# 10_LMS3_RF.net
KiCad netlist of a schematic drawn in Altium Designer
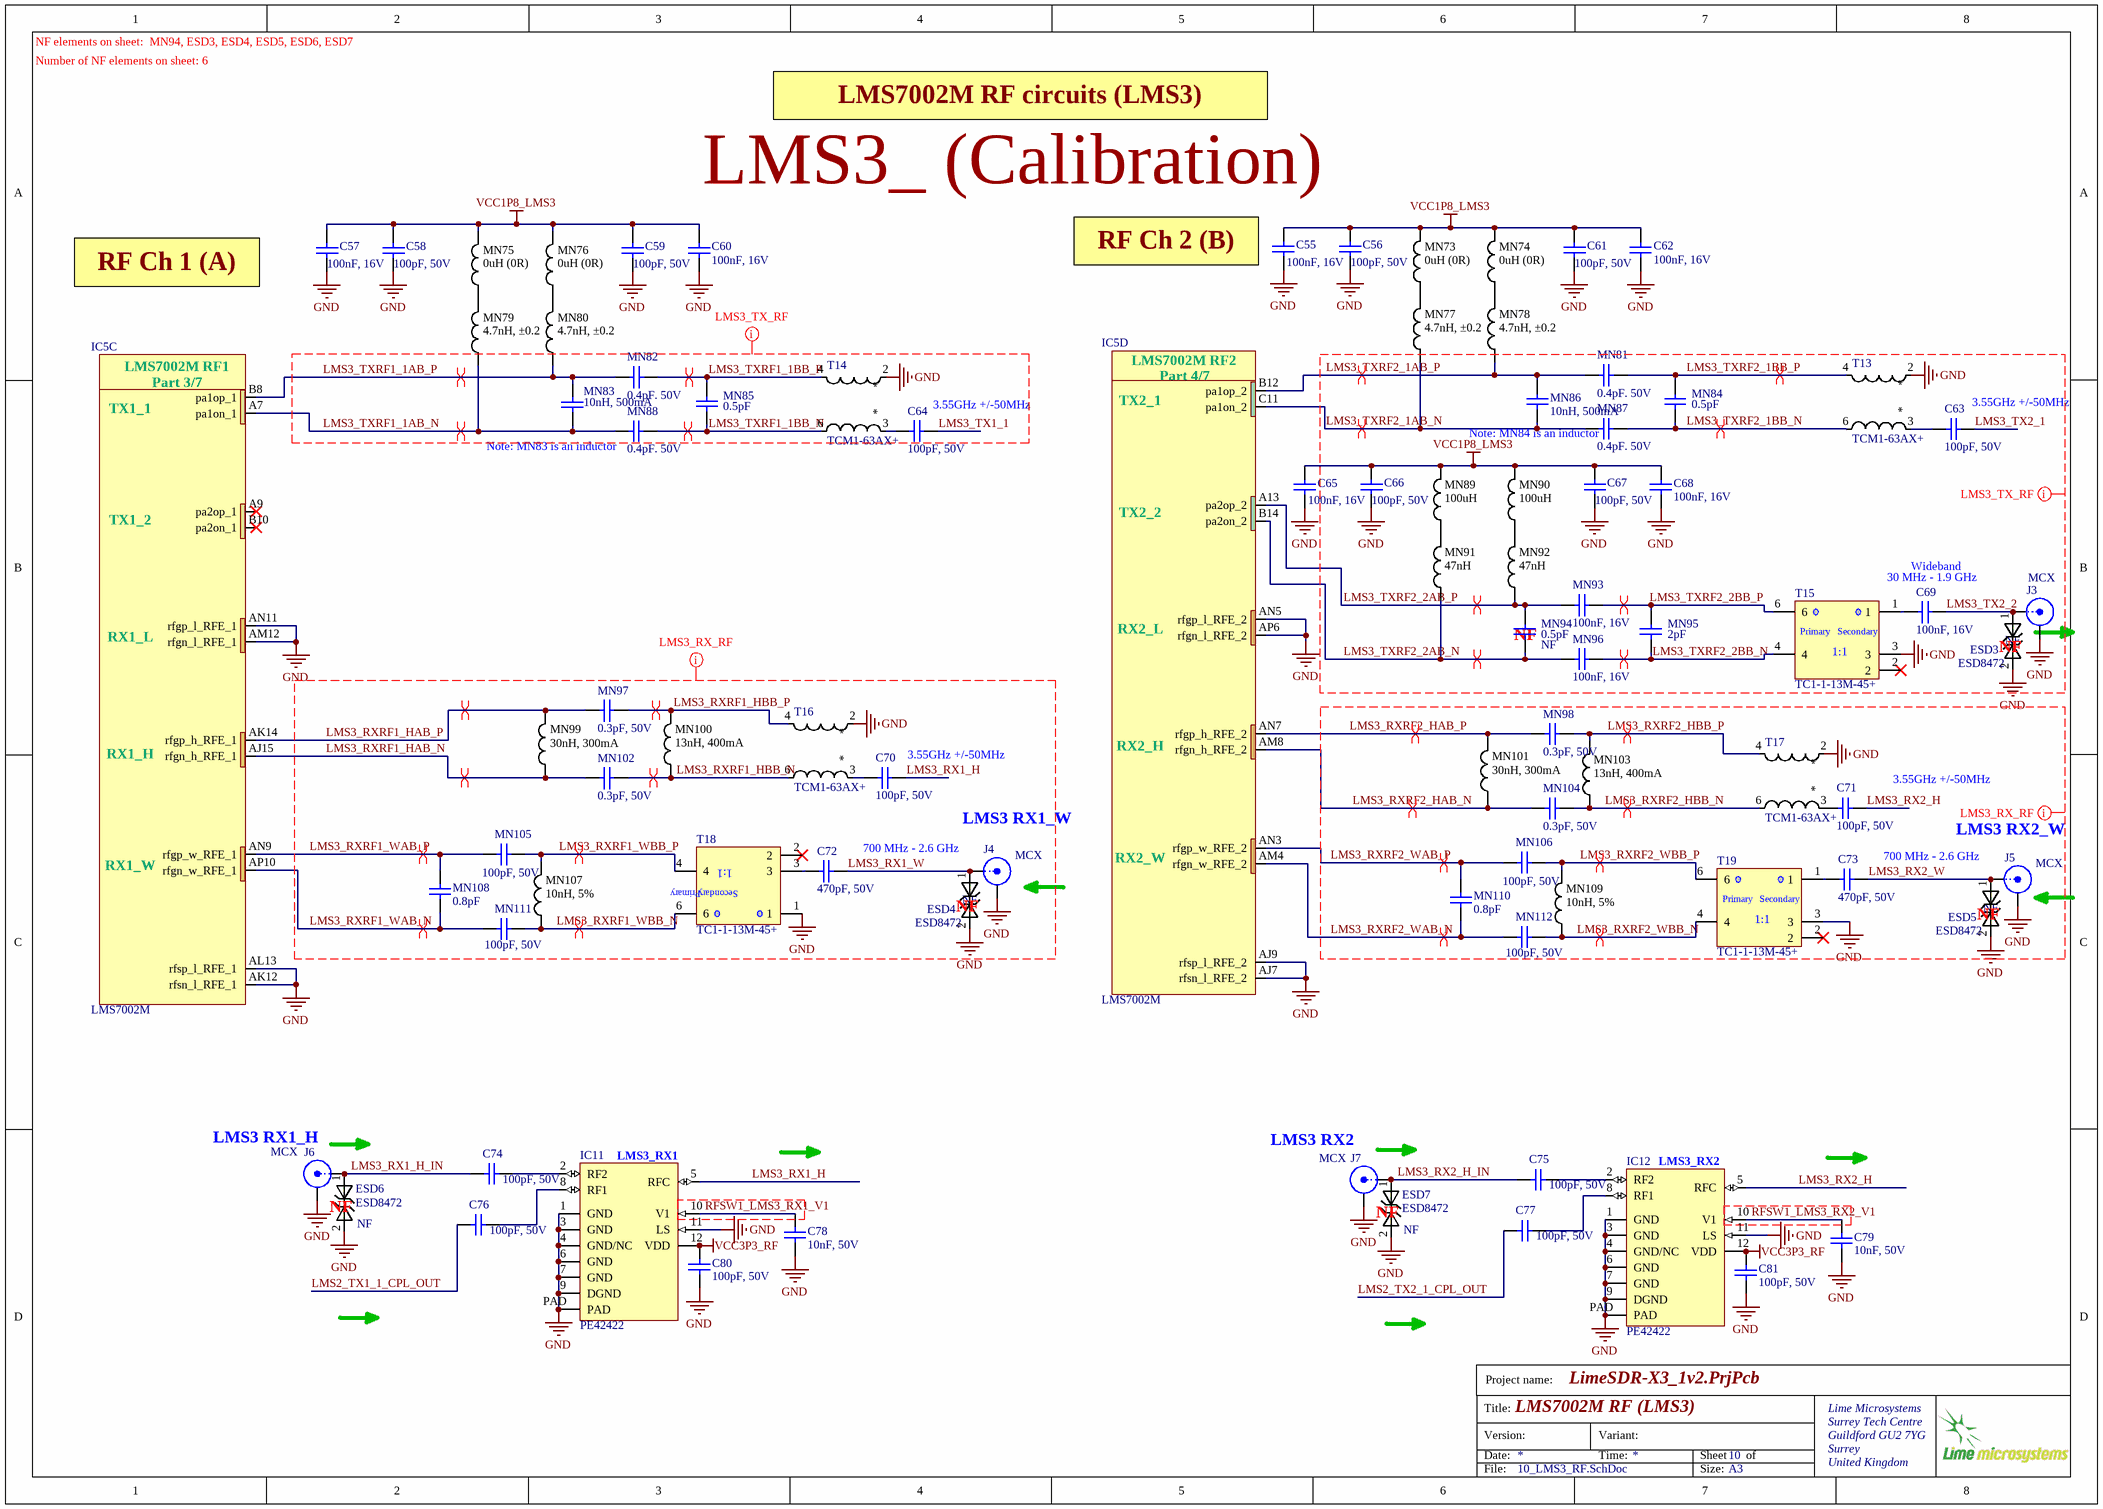
[diagram p0: 10_LMS3_RF.SchDoc]

(export (version "E")
  (design (tool "Eeschema 10.0.6"))
  (components
    (comp (ref "C55")
      (value "100nF, 16V")
      (footprint "CAP0402")
      (fields (field (name "MANUFACTURER") "Murata Electronics") (field (name "TOLERANCE") "10 %"))
      (libsource (lib "") (part "Cap_0402_9"))
    )
    (comp (ref "C56")
      (value "100pF, 50V")
      (footprint "CAP0402")
      (fields (field (name "MANUFACTURER") "Yageo") (field (name "TOLERANCE") "±5%"))
      (libsource (lib "") (part "Cap_0402_5"))
    )
    (comp (ref "C57")
      (value "100nF, 16V")
      (footprint "CAP0402")
      (fields (field (name "MANUFACTURER") "Murata Electronics") (field (name "TOLERANCE") "10 %"))
      (libsource (lib "") (part "Cap_0402_1"))
    )
    (comp (ref "C58")
      (value "100pF, 50V")
      (footprint "CAP0402")
      (fields (field (name "MANUFACTURER") "Yageo") (field (name "TOLERANCE") "±5%"))
      (libsource (lib "") (part "Cap_0402_5"))
    )
    (comp (ref "C59")
      (value "100pF, 50V")
      (footprint "CAP0402")
      (fields (field (name "MANUFACTURER") "Yageo") (field (name "TOLERANCE") "±5%"))
      (libsource (lib "") (part "Cap_0402_5"))
    )
    (comp (ref "C60")
      (value "100nF, 16V")
      (footprint "CAP0402")
      (fields (field (name "MANUFACTURER") "Murata Electronics") (field (name "TOLERANCE") "10 %"))
      (libsource (lib "") (part "Cap_0402_1"))
    )
    (comp (ref "C61")
      (value "100pF, 50V")
      (footprint "CAP0402")
      (fields (field (name "MANUFACTURER") "Yageo") (field (name "TOLERANCE") "±5%"))
      (libsource (lib "") (part "Cap_0402_5"))
    )
    (comp (ref "C62")
      (value "100nF, 16V")
      (footprint "CAP0402")
      (fields (field (name "MANUFACTURER") "Murata Electronics") (field (name "TOLERANCE") "10 %"))
      (libsource (lib "") (part "Cap_0402_9"))
    )
    (comp (ref "C63")
      (value "100pF, 50V")
      (footprint "CAP0402")
      (fields (field (name "TOLERANCE") "±5%") (field (name "MANUFACTURER") "Yageo"))
      (libsource (lib "") (part "Cap_0402_5"))
    )
    (comp (ref "C64")
      (value "100pF, 50V")
      (footprint "CAP0402")
      (fields (field (name "TOLERANCE") "±5%") (field (name "MANUFACTURER") "Yageo"))
      (libsource (lib "") (part "Cap_0402_5"))
    )
    (comp (ref "C65")
      (value "100nF, 16V")
      (footprint "CAP0402")
      (fields (field (name "MANUFACTURER") "Murata Electronics") (field (name "TOLERANCE") "10 %"))
      (libsource (lib "") (part "Cap_0402_6"))
    )
    (comp (ref "C66")
      (value "100pF, 50V")
      (footprint "CAP0402")
      (fields (field (name "MANUFACTURER") "Yageo") (field (name "TOLERANCE") "±5%"))
      (libsource (lib "") (part "Cap_0402_5"))
    )
    (comp (ref "C67")
      (value "100pF, 50V")
      (footprint "CAP0402")
      (fields (field (name "MANUFACTURER") "Yageo") (field (name "TOLERANCE") "±5%"))
      (libsource (lib "") (part "Cap_0402_5"))
    )
    (comp (ref "C68")
      (value "100nF, 16V")
      (footprint "CAP0402")
      (fields (field (name "MANUFACTURER") "Murata Electronics") (field (name "TOLERANCE") "10 %"))
      (libsource (lib "") (part "Cap_0402_6"))
    )
    (comp (ref "C69")
      (value "100nF, 16V")
      (footprint "CAP0402")
      (fields (field (name "MANUFACTURER") "Murata Electronics") (field (name "TOLERANCE") "10 %"))
      (libsource (lib "") (part "Cap_0402_12"))
    )
    (comp (ref "C70")
      (value "100pF, 50V")
      (footprint "CAP0402")
      (fields (field (name "TOLERANCE") "±5%") (field (name "MANUFACTURER") "Yageo"))
      (libsource (lib "LimeMicroAltiumLib_schLib") (part "Cap_0402"))
    )
    (comp (ref "C71")
      (value "100pF, 50V")
      (footprint "CAP0402")
      (fields (field (name "TOLERANCE") "±5%") (field (name "MANUFACTURER") "Yageo"))
      (libsource (lib "LimeMicroAltiumLib_schLib") (part "Cap_0402"))
    )
    (comp (ref "C72")
      (value "470pF, 50V")
      (footprint "CAP0402")
      (fields
        (field (name "MANUFACTURER PART NUMBER") "C1005C0G1H471J050BA")
        (field (name "TOLERANCE") "±5%")
        (field (name "MANUFACTURER") "TDK Corporation")
      )
      (libsource (lib "") (part "Cap_0402_4"))
    )
    (comp (ref "C73")
      (value "470pF, 50V")
      (footprint "CAP0402")
      (fields
        (field (name "MANUFACTURER PART NUMBER") "C1005C0G1H471J050BA")
        (field (name "TOLERANCE") "±5%")
        (field (name "MANUFACTURER") "TDK Corporation")
      )
      (libsource (lib "") (part "Cap_0402_4"))
    )
    (comp (ref "C74")
      (value "100pF, 50V")
      (footprint "CAP0402")
      (fields (field (name "TOLERANCE") "±5%") (field (name "MANUFACTURER") "Yageo"))
      (libsource (lib "") (part "Cap_0402_7"))
    )
    (comp (ref "C75")
      (value "100pF, 50V")
      (footprint "CAP0402")
      (fields (field (name "TOLERANCE") "±5%") (field (name "MANUFACTURER") "Yageo"))
      (libsource (lib "") (part "Cap_0402_7"))
    )
    (comp (ref "C76")
      (value "100pF, 50V")
      (footprint "CAP0402")
      (fields (field (name "TOLERANCE") "±5%") (field (name "MANUFACTURER") "Yageo"))
      (libsource (lib "") (part "Cap_0402_7"))
    )
    (comp (ref "C77")
      (value "100pF, 50V")
      (footprint "CAP0402")
      (fields (field (name "TOLERANCE") "±5%") (field (name "MANUFACTURER") "Yageo"))
      (libsource (lib "") (part "Cap_0402_7"))
    )
    (comp (ref "C78")
      (value "10nF, 50V")
      (footprint "CAP0402")
      (fields
        (field (name "MANUFACTURER") "Murata Electronics North America")
        (field (name "TOLERANCE") "±10%")
      )
      (libsource (lib "") (part "Cap_0402_1"))
    )
    (comp (ref "C79")
      (value "10nF, 50V")
      (footprint "CAP0402")
      (fields
        (field (name "MANUFACTURER") "Murata Electronics North America")
        (field (name "TOLERANCE") "±10%")
      )
      (libsource (lib "") (part "Cap_0402_1"))
    )
    (comp (ref "C80")
      (value "100pF, 50V")
      (footprint "CAP0402")
      (fields (field (name "TOLERANCE") "±5%") (field (name "MANUFACTURER") "Yageo"))
      (libsource (lib "") (part "Cap_0402_10"))
    )
    (comp (ref "C81")
      (value "100pF, 50V")
      (footprint "CAP0402")
      (fields (field (name "TOLERANCE") "±5%") (field (name "MANUFACTURER") "Yageo"))
      (libsource (lib "") (part "Cap_0402_10"))
    )
    (comp (ref "ESD3")
      (value "ESD8472")
      (footprint "ESD8472_X3DFN2")
      (fields (field (name "MANUFACTURER") "ON Semiconductor") (field (name "ASSEMBLY INFO") "NF"))
      (libsource (lib "LimeMicroAltiumLib_schLib") (part "ESD8472"))
    )
    (comp (ref "ESD4")
      (value "ESD8472")
      (footprint "ESD8472_X3DFN2")
      (fields (field (name "MANUFACTURER") "ON Semiconductor") (field (name "ASSEMBLY INFO") "NF"))
      (libsource (lib "LimeMicroAltiumLib_schLib") (part "ESD8472"))
    )
    (comp (ref "ESD5")
      (value "ESD8472")
      (footprint "ESD8472_X3DFN2")
      (fields (field (name "MANUFACTURER") "ON Semiconductor") (field (name "ASSEMBLY INFO") "NF"))
      (libsource (lib "LimeMicroAltiumLib_schLib") (part "ESD8472"))
    )
    (comp (ref "ESD6")
      (value "ESD8472")
      (footprint "ESD8472_X3DFN2")
      (fields (field (name "MANUFACTURER") "ON Semiconductor") (field (name "ASSEMBLY INFO") "NF"))
      (libsource (lib "LimeMicroAltiumLib_schLib") (part "ESD8472"))
    )
    (comp (ref "ESD7")
      (value "ESD8472")
      (footprint "ESD8472_X3DFN2")
      (fields (field (name "MANUFACTURER") "ON Semiconductor") (field (name "ASSEMBLY INFO") "NF"))
      (libsource (lib "LimeMicroAltiumLib_schLib") (part "ESD8472"))
    )
    (comp (ref "IC5")
      (value "LMS7002M")
      (footprint "LMS7002M_v5")
      (description "Schematic symbol revision 4. Default footprint - 0.31mm pad")
      (fields (field (name "MANUFACTURER") "Lime Microsystems"))
      (libsource (lib "LimeMicroAltiumLib_schLib_r04") (part "LMS7002Mr4"))
    )
    (comp (ref "IC11")
      (value "PE42422")
      (footprint "PE42422_QFN12")
      (fields (field (name "MANUFACTURER") "Peregrine Semiconductor"))
      (libsource (lib "LimeMicroAltiumLib_schLib") (part "PE42422"))
    )
    (comp (ref "IC12")
      (value "PE42422")
      (footprint "PE42422_QFN12")
      (fields (field (name "MANUFACTURER") "Peregrine Semiconductor"))
      (libsource (lib "LimeMicroAltiumLib_schLib") (part "PE42422"))
    )
    (comp (ref "J3")
      (value "MCX")
      (footprint "MCX_connector_vertical_SM")
      (fields (field (name "MANUFACTURER") "Bel Cinch"))
      (libsource (lib "LimeMicroAltiumLib_schLib") (part "RF_IF_connector"))
    )
    (comp (ref "J4")
      (value "MCX")
      (footprint "MCX_connector_vertical_SM")
      (fields (field (name "MANUFACTURER") "Bel Cinch"))
      (libsource (lib "LimeMicroAltiumLib_schLib") (part "RF_IF_connector"))
    )
    (comp (ref "J5")
      (value "MCX")
      (footprint "MCX_connector_vertical_SM")
      (fields (field (name "MANUFACTURER") "Bel Cinch"))
      (libsource (lib "LimeMicroAltiumLib_schLib") (part "RF_IF_connector"))
    )
    (comp (ref "J6")
      (value "MCX")
      (footprint "MCX_connector_vertical_SM")
      (fields (field (name "MANUFACTURER") "Bel Cinch"))
      (libsource (lib "LimeMicroAltiumLib_schLib") (part "RF_IF_connector"))
    )
    (comp (ref "J7")
      (value "MCX")
      (footprint "MCX_connector_vertical_SM")
      (fields (field (name "MANUFACTURER") "Bel Cinch"))
      (libsource (lib "LimeMicroAltiumLib_schLib") (part "RF_IF_connector"))
    )
    (comp (ref "MN73")
      (value "0uH (0R)")
      (footprint "RES0603")
      (fields
        (field (name "MANUFACTURER") "Panasonic Electronic Components")
        (field (name "MANUFACTURER PART NUMBER") "ERJ-3GEY0R00V")
        (field (name "TOLERANCE") "Jumper")
      )
      (libsource (lib "") (part "Inductor_0603_2"))
    )
    (comp (ref "MN74")
      (value "0uH (0R)")
      (footprint "RES0603")
      (fields
        (field (name "MANUFACTURER") "Panasonic Electronic Components")
        (field (name "MANUFACTURER PART NUMBER") "ERJ-3GEY0R00V")
        (field (name "TOLERANCE") "Jumper")
      )
      (libsource (lib "") (part "Inductor_0603_2"))
    )
    (comp (ref "MN75")
      (value "0uH (0R)")
      (footprint "RES0603")
      (fields
        (field (name "MANUFACTURER") "Panasonic Electronic Components")
        (field (name "MANUFACTURER PART NUMBER") "ERJ-3GEY0R00V")
        (field (name "TOLERANCE") "Jumper")
      )
      (libsource (lib "") (part "Inductor_0603_2"))
    )
    (comp (ref "MN76")
      (value "0uH (0R)")
      (footprint "RES0603")
      (fields
        (field (name "MANUFACTURER") "Panasonic Electronic Components")
        (field (name "MANUFACTURER PART NUMBER") "ERJ-3GEY0R00V")
        (field (name "TOLERANCE") "Jumper")
      )
      (libsource (lib "") (part "Inductor_0603_2"))
    )
    (comp (ref "MN77")
      (value "4.7nH, ±0.2")
      (footprint "RES0402")
      (fields (field (name "MANUFACTURER") "Murata"))
      (libsource (lib "") (part "Inductor_0603_2"))
    )
    (comp (ref "MN78")
      (value "4.7nH, ±0.2")
      (footprint "RES0402")
      (fields (field (name "MANUFACTURER") "Murata"))
      (libsource (lib "") (part "Inductor_0603_2"))
    )
    (comp (ref "MN79")
      (value "4.7nH, ±0.2")
      (footprint "RES0402")
      (fields (field (name "MANUFACTURER") "Murata"))
      (libsource (lib "") (part "Inductor_0603_2"))
    )
    (comp (ref "MN80")
      (value "4.7nH, ±0.2")
      (footprint "RES0402")
      (fields (field (name "MANUFACTURER") "Murata"))
      (libsource (lib "") (part "Inductor_0603_2"))
    )
    (comp (ref "MN81")
      (value "0.4pF. 50V")
      (footprint "CAP0402")
      (fields (field (name "MANUFACTURER") "Murata"))
      (libsource (lib "") (part "Cap_0402_6"))
    )
    (comp (ref "MN82")
      (value "0.4pF. 50V")
      (footprint "CAP0402")
      (fields (field (name "MANUFACTURER") "Murata"))
      (libsource (lib "") (part "Cap_0402_6"))
    )
    (comp (ref "MN83")
      (value "10nH, 500mA")
      (footprint "CAP0402")
      (fields (field (name "MANUFACTURER") "Murata") (field (name "TOLERANCE") "2%"))
      (libsource (lib "") (part "Cap_0402_1"))
    )
    (comp (ref "MN84")
      (value "0.5pF")
      (footprint "CAP0402")
      (fields (field (name "TOLERANCE") "±0.25pF") (field (name "MANUFACTURER") "Yageo"))
      (libsource (lib "") (part "Cap_0402_3"))
    )
    (comp (ref "MN85")
      (value "0.5pF")
      (footprint "CAP0402")
      (fields (field (name "TOLERANCE") "±0.25pF") (field (name "MANUFACTURER") "Yageo"))
      (libsource (lib "") (part "Cap_0402_3"))
    )
    (comp (ref "MN86")
      (value "10nH, 500mA")
      (footprint "CAP0402")
      (fields (field (name "MANUFACTURER") "Murata") (field (name "TOLERANCE") "2%"))
      (libsource (lib "") (part "Cap_0402_1"))
    )
    (comp (ref "MN87")
      (value "0.4pF. 50V")
      (footprint "CAP0402")
      (fields (field (name "MANUFACTURER") "Murata"))
      (libsource (lib "") (part "Cap_0402_2"))
    )
    (comp (ref "MN88")
      (value "0.4pF. 50V")
      (footprint "CAP0402")
      (fields (field (name "MANUFACTURER") "Murata"))
      (libsource (lib "") (part "Cap_0402_2"))
    )
    (comp (ref "MN89")
      (value "100uH")
      (footprint "RES0603")
      (fields
        (field (name "MANUFACTURER") "TDK Corporation")
        (field (name "MANUFACTURER PART NUMBER") "GLFR1608T101M-LR")
        (field (name "TOLERANCE") "±20%")
      )
      (libsource (lib "LimeMicroAltiumLib_schLib") (part "Inductor_0603"))
    )
    (comp (ref "MN90")
      (value "100uH")
      (footprint "RES0603")
      (fields
        (field (name "MANUFACTURER") "TDK Corporation")
        (field (name "MANUFACTURER PART NUMBER") "GLFR1608T101M-LR")
        (field (name "TOLERANCE") "±20%")
      )
      (libsource (lib "LimeMicroAltiumLib_schLib") (part "Inductor_0603"))
    )
    (comp (ref "MN91")
      (value "47nH")
      (footprint "RES0402")
      (fields (field (name "MANUFACTURER") "COILCRAFT"))
      (libsource (lib "LimeMicroAltiumLib_schLib") (part "Inductor_0603"))
    )
    (comp (ref "MN92")
      (value "47nH")
      (footprint "RES0402")
      (fields (field (name "MANUFACTURER") "COILCRAFT"))
      (libsource (lib "LimeMicroAltiumLib_schLib") (part "Inductor_0603"))
    )
    (comp (ref "MN93")
      (value "100nF, 16V")
      (footprint "CAP0402")
      (fields (field (name "MANUFACTURER") "Murata Electronics") (field (name "TOLERANCE") "10 %"))
      (libsource (lib "") (part "Cap_0402_9"))
    )
    (comp (ref "MN94")
      (value "0.5pF")
      (footprint "CAP0402")
      (fields
        (field (name "ASSEMBLY INFO") "NF")
        (field (name "TOLERANCE") "±0.25pF")
        (field (name "MANUFACTURER") "Yageo")
      )
      (libsource (lib "") (part "Cap_0402_6"))
    )
    (comp (ref "MN95")
      (value "2pF")
      (footprint "CAP0402")
      (fields (field (name "MANUFACTURER PART NUMBER") "04025U2R0BAT2A") (field (name "MANUFACTURER") "AVX"))
      (libsource (lib "") (part "Cap_0402_6"))
    )
    (comp (ref "MN96")
      (value "100nF, 16V")
      (footprint "CAP0402")
      (fields (field (name "MANUFACTURER") "Murata Electronics") (field (name "TOLERANCE") "10 %"))
      (libsource (lib "") (part "Cap_0402_8"))
    )
    (comp (ref "MN97")
      (value "0.3pF, 50V")
      (footprint "CAP0402")
      (fields (field (name "MANUFACTURER") "Johanson"))
      (libsource (lib "") (part "Cap_0402_11"))
    )
    (comp (ref "MN98")
      (value "0.3pF, 50V")
      (footprint "CAP0402")
      (fields (field (name "MANUFACTURER") "Johanson"))
      (libsource (lib "") (part "Cap_0402_11"))
    )
    (comp (ref "MN99")
      (value "30nH, 300mA")
      (footprint "RES0402")
      (fields (field (name "MANUFACTURER") "TDK") (field (name "TOLERANCE") "5%"))
      (libsource (lib "LimeMicroAltiumLib_schLib") (part "Inductor_0603"))
    )
    (comp (ref "MN100")
      (value "13nH, 400mA")
      (footprint "RES0402")
      (fields (field (name "MANUFACTURER") "TDK") (field (name "TOLERANCE") "5%"))
      (libsource (lib "") (part "Inductor_0603_1"))
    )
    (comp (ref "MN101")
      (value "30nH, 300mA")
      (footprint "RES0402")
      (fields (field (name "MANUFACTURER") "TDK") (field (name "TOLERANCE") "5%"))
      (libsource (lib "LimeMicroAltiumLib_schLib") (part "Inductor_0603"))
    )
    (comp (ref "MN102")
      (value "0.3pF, 50V")
      (footprint "CAP0402")
      (fields (field (name "MANUFACTURER") "Johanson"))
      (libsource (lib "") (part "Cap_0402_11"))
    )
    (comp (ref "MN103")
      (value "13nH, 400mA")
      (footprint "RES0402")
      (fields (field (name "MANUFACTURER") "TDK") (field (name "TOLERANCE") "5%"))
      (libsource (lib "") (part "Inductor_0603_1"))
    )
    (comp (ref "MN104")
      (value "0.3pF, 50V")
      (footprint "CAP0402")
      (fields (field (name "MANUFACTURER") "Johanson"))
      (libsource (lib "") (part "Cap_0402_11"))
    )
    (comp (ref "MN105")
      (value "100pF, 50V")
      (footprint "CAP0402")
      (fields (field (name "TOLERANCE") "±5%") (field (name "MANUFACTURER") "Yageo"))
      (libsource (lib "") (part "Cap_0402_4"))
    )
    (comp (ref "MN106")
      (value "100pF, 50V")
      (footprint "CAP0402")
      (fields (field (name "TOLERANCE") "±5%") (field (name "MANUFACTURER") "Yageo"))
      (libsource (lib "") (part "Cap_0402_4"))
    )
    (comp (ref "MN107")
      (value "10nH, 5%")
      (footprint "RES0402")
      (fields (field (name "MANUFACTURER") "COILCRAFT"))
      (libsource (lib "") (part "Inductor_0603_3"))
    )
    (comp (ref "MN108")
      (value "0.8pF")
      (footprint "CAP0402")
      (fields
        (field (name "TOLERANCE") "±0.1pF")
        (field (name "MANUFACTURER") "Murata Electronics North America")
        (field (name "MANUFACTURER PART NUMBER") "GRM1555C1HR80BA01D")
      )
      (libsource (lib "") (part "Cap_0402_4"))
    )
    (comp (ref "MN109")
      (value "10nH, 5%")
      (footprint "RES0402")
      (fields (field (name "MANUFACTURER") "COILCRAFT"))
      (libsource (lib "") (part "Inductor_0603_3"))
    )
    (comp (ref "MN110")
      (value "0.8pF")
      (footprint "CAP0402")
      (fields
        (field (name "TOLERANCE") "±0.1pF")
        (field (name "MANUFACTURER") "Murata Electronics North America")
        (field (name "MANUFACTURER PART NUMBER") "GRM1555C1HR80BA01D")
      )
      (libsource (lib "") (part "Cap_0402_4"))
    )
    (comp (ref "MN111")
      (value "100pF, 50V")
      (footprint "CAP0402")
      (fields (field (name "TOLERANCE") "±5%") (field (name "MANUFACTURER") "Yageo"))
      (libsource (lib "") (part "Cap_0402_4"))
    )
    (comp (ref "MN112")
      (value "100pF, 50V")
      (footprint "CAP0402")
      (fields (field (name "TOLERANCE") "±5%") (field (name "MANUFACTURER") "Yageo"))
      (libsource (lib "") (part "Cap_0402_4"))
    )
    (comp (ref "T13")
      (value "TCM1-63AX+")
      (footprint "TCM1-63AX+_v2")
      (fields (field (name "MANUFACTURER") "Mini-circuits"))
      (libsource (lib "") (part "Balun_v2_1"))
    )
    (comp (ref "T14")
      (value "TCM1-63AX+")
      (footprint "TCM1-63AX+_v2")
      (fields (field (name "MANUFACTURER") "Mini-circuits"))
      (libsource (lib "") (part "Balun_v2_1"))
    )
    (comp (ref "T15")
      (value "TC1-1-13M-45+")
      (footprint "TC1-1-13MA+_JA4220-AL_")
      (fields (field (name "MANUFACTURER") "Minicircuits"))
      (libsource (lib "") (part "TC1-1-13M+_1"))
    )
    (comp (ref "T16")
      (value "TCM1-63AX+")
      (footprint "TCM1-63AX+_v2")
      (fields (field (name "MANUFACTURER") "Mini-circuits"))
      (libsource (lib "LimeMicroAltiumLib_schLib") (part "Balun_v2"))
    )
    (comp (ref "T17")
      (value "TCM1-63AX+")
      (footprint "TCM1-63AX+_v2")
      (fields (field (name "MANUFACTURER") "Mini-circuits"))
      (libsource (lib "LimeMicroAltiumLib_schLib") (part "Balun_v2"))
    )
    (comp (ref "T18")
      (value "TC1-1-13M-45+")
      (footprint "TC1-1-13MA+_JA4220-AL_")
      (fields (field (name "MANUFACTURER") "Minicircuits"))
      (libsource (lib "LimeMicroAltiumLib_schLib") (part "TC1-1-13M+"))
    )
    (comp (ref "T19")
      (value "TC1-1-13M-45+")
      (footprint "TC1-1-13MA+_JA4220-AL_")
      (fields (field (name "MANUFACTURER") "Minicircuits"))
      (libsource (lib "") (part "TC1-1-13M+_1"))
    )
  )
  (nets
    (net (code "1") (name "/LMS2_TX1_1_CPL_OUT") (class "Default")
      (node (ref "C76") (pin "2") (pinfunction "2_2") (pintype "passive"))
    )
    (net (code "2") (name "/LMS2_TX2_1_CPL_OUT") (class "Default")
      (node (ref "C77") (pin "2") (pinfunction "2_2") (pintype "passive"))
    )
    (net (code "3") (name "/LMS3_RX1_H") (class "Default")
      (node (ref "C70") (pin "1") (pinfunction "1_1") (pintype "passive"))
      (node (ref "IC11") (pin "5") (pinfunction "RFC_5") (pintype "bidirectional"))
    )
    (net (code "4") (name "/LMS3_RX1_H_IN") (class "Default")
      (node (ref "C74") (pin "2") (pinfunction "2_2") (pintype "passive"))
      (node (ref "ESD6") (pin "1") (pinfunction "1_1") (pintype "passive"))
      (node (ref "J6") (pin "1") (pinfunction "X_1") (pintype "passive"))
    )
    (net (code "5") (name "/LMS3_RX1_W") (class "Default")
      (node (ref "C72") (pin "1") (pinfunction "1_1") (pintype "passive"))
      (node (ref "ESD4") (pin "1") (pinfunction "1_1") (pintype "passive"))
      (node (ref "J4") (pin "1") (pinfunction "X_1") (pintype "passive"))
    )
    (net (code "6") (name "/LMS3_RX2_H") (class "Default")
      (node (ref "C71") (pin "1") (pinfunction "1_1") (pintype "passive"))
      (node (ref "IC12") (pin "5") (pinfunction "RFC_5") (pintype "bidirectional"))
    )
    (net (code "7") (name "/LMS3_RX2_H_IN") (class "Default")
      (node (ref "C75") (pin "2") (pinfunction "2_2") (pintype "passive"))
      (node (ref "ESD7") (pin "1") (pinfunction "1_1") (pintype "passive"))
      (node (ref "J7") (pin "1") (pinfunction "X_1") (pintype "passive"))
    )
    (net (code "8") (name "/LMS3_RX2_W") (class "Default")
      (node (ref "C73") (pin "1") (pinfunction "1_1") (pintype "passive"))
      (node (ref "ESD5") (pin "1") (pinfunction "1_1") (pintype "passive"))
      (node (ref "J5") (pin "1") (pinfunction "X_1") (pintype "passive"))
    )
    (net (code "9") (name "/LMS3_RXRF1_HAB_N") (class "Default")
      (node (ref "IC5") (pin "AJ15") (pinfunction "rfgn_h_RFE_1_AJ15") (pintype "passive"))
      (node (ref "MN102") (pin "2") (pinfunction "2_2") (pintype "passive"))
      (node (ref "MN99") (pin "1") (pinfunction "1_1") (pintype "passive"))
    )
    (net (code "10") (name "/LMS3_RXRF1_HAB_P") (class "Default")
      (node (ref "IC5") (pin "AK14") (pinfunction "rfgp_h_RFE_1_AK14") (pintype "passive"))
      (node (ref "MN97") (pin "2") (pinfunction "2_2") (pintype "passive"))
      (node (ref "MN99") (pin "2") (pinfunction "2_2") (pintype "passive"))
    )
    (net (code "11") (name "/LMS3_RXRF1_HBB_N") (class "Default")
      (node (ref "MN100") (pin "1") (pinfunction "1_1") (pintype "passive"))
      (node (ref "MN102") (pin "1") (pinfunction "1_1") (pintype "passive"))
      (node (ref "T16") (pin "6") (pinfunction "6_6") (pintype "passive"))
    )
    (net (code "12") (name "/LMS3_RXRF1_HBB_P") (class "Default")
      (node (ref "MN100") (pin "2") (pinfunction "2_2") (pintype "passive"))
      (node (ref "MN97") (pin "1") (pinfunction "1_1") (pintype "passive"))
      (node (ref "T16") (pin "4") (pinfunction "4_4") (pintype "passive"))
    )
    (net (code "13") (name "/LMS3_RXRF1_WAB_N") (class "Default")
      (node (ref "IC5") (pin "AP10") (pinfunction "rfgn_w_RFE_1_AP10") (pintype "passive"))
      (node (ref "MN108") (pin "2") (pinfunction "2_2") (pintype "passive"))
      (node (ref "MN111") (pin "2") (pinfunction "2_2") (pintype "passive"))
    )
    (net (code "14") (name "/LMS3_RXRF1_WAB_P") (class "Default")
      (node (ref "IC5") (pin "AN9") (pinfunction "rfgp_w_RFE_1_AN9") (pintype "passive"))
      (node (ref "MN105") (pin "2") (pinfunction "2_2") (pintype "passive"))
      (node (ref "MN108") (pin "1") (pinfunction "1_1") (pintype "passive"))
    )
    (net (code "15") (name "/LMS3_RXRF1_WBB_N") (class "Default")
      (node (ref "MN107") (pin "1") (pinfunction "1_1") (pintype "passive"))
      (node (ref "MN111") (pin "1") (pinfunction "1_1") (pintype "passive"))
      (node (ref "T18") (pin "6") (pinfunction "6_6") (pintype "passive"))
    )
    (net (code "16") (name "/LMS3_RXRF1_WBB_P") (class "Default")
      (node (ref "MN105") (pin "1") (pinfunction "1_1") (pintype "passive"))
      (node (ref "MN107") (pin "2") (pinfunction "2_2") (pintype "passive"))
      (node (ref "T18") (pin "4") (pinfunction "4_4") (pintype "passive"))
    )
    (net (code "18") (name "/LMS3_RXRF2_HAB_N") (class "Default")
      (node (ref "IC5") (pin "AM8") (pinfunction "rfgn_h_RFE_2_AM8") (pintype "passive"))
      (node (ref "MN101") (pin "1") (pinfunction "1_1") (pintype "passive"))
      (node (ref "MN104") (pin "2") (pinfunction "2_2") (pintype "passive"))
    )
    (net (code "19") (name "/LMS3_RXRF2_HAB_P") (class "Default")
      (node (ref "IC5") (pin "AN7") (pinfunction "rfgp_h_RFE_2_AN7") (pintype "passive"))
      (node (ref "MN101") (pin "2") (pinfunction "2_2") (pintype "passive"))
      (node (ref "MN98") (pin "2") (pinfunction "2_2") (pintype "passive"))
    )
    (net (code "20") (name "/LMS3_RXRF2_HBB_N") (class "Default")
      (node (ref "MN103") (pin "1") (pinfunction "1_1") (pintype "passive"))
      (node (ref "MN104") (pin "1") (pinfunction "1_1") (pintype "passive"))
      (node (ref "T17") (pin "6") (pinfunction "6_6") (pintype "passive"))
    )
    (net (code "21") (name "/LMS3_RXRF2_HBB_P") (class "Default")
      (node (ref "MN103") (pin "2") (pinfunction "2_2") (pintype "passive"))
      (node (ref "MN98") (pin "1") (pinfunction "1_1") (pintype "passive"))
      (node (ref "T17") (pin "4") (pinfunction "4_4") (pintype "passive"))
    )
    (net (code "22") (name "/LMS3_RXRF2_WAB_N") (class "Default")
      (node (ref "IC5") (pin "AM4") (pinfunction "rfgn_w_RFE_2_AM4") (pintype "passive"))
      (node (ref "MN110") (pin "2") (pinfunction "2_2") (pintype "passive"))
      (node (ref "MN112") (pin "2") (pinfunction "2_2") (pintype "passive"))
    )
    (net (code "23") (name "/LMS3_RXRF2_WAB_P") (class "Default")
      (node (ref "IC5") (pin "AN3") (pinfunction "rfgp_w_RFE_2_AN3") (pintype "passive"))
      (node (ref "MN106") (pin "2") (pinfunction "2_2") (pintype "passive"))
      (node (ref "MN110") (pin "1") (pinfunction "1_1") (pintype "passive"))
    )
    (net (code "24") (name "/LMS3_RXRF2_WBB_N") (class "Default")
      (node (ref "MN109") (pin "1") (pinfunction "1_1") (pintype "passive"))
      (node (ref "MN112") (pin "1") (pinfunction "1_1") (pintype "passive"))
      (node (ref "T19") (pin "4") (pinfunction "4_4") (pintype "passive"))
    )
    (net (code "25") (name "/LMS3_RXRF2_WBB_P") (class "Default")
      (node (ref "MN106") (pin "1") (pinfunction "1_1") (pintype "passive"))
      (node (ref "MN109") (pin "2") (pinfunction "2_2") (pintype "passive"))
      (node (ref "T19") (pin "6") (pinfunction "6_6") (pintype "passive"))
    )
    (net (code "26") (name "/LMS3_TX1_1") (class "Default")
      (node (ref "C64") (pin "1") (pinfunction "1_1") (pintype "passive"))
    )
    (net (code "27") (name "/LMS3_TX2_1") (class "Default")
      (node (ref "C63") (pin "1") (pinfunction "1_1") (pintype "passive"))
    )
    (net (code "28") (name "/LMS3_TX2_2") (class "Default")
      (node (ref "C69") (pin "1") (pinfunction "1_1") (pintype "passive"))
      (node (ref "ESD3") (pin "1") (pinfunction "1_1") (pintype "passive"))
      (node (ref "J3") (pin "1") (pinfunction "X_1") (pintype "passive"))
    )
    (net (code "29") (name "/LMS3_TXRF1_1AB_N") (class "Default")
      (node (ref "IC5") (pin "A7") (pinfunction "pa1on_1_A7") (pintype "passive"))
      (node (ref "MN79") (pin "1") (pinfunction "1_1") (pintype "passive"))
      (node (ref "MN83") (pin "2") (pinfunction "2_2") (pintype "passive"))
      (node (ref "MN88") (pin "2") (pinfunction "2_2") (pintype "passive"))
    )
    (net (code "30") (name "/LMS3_TXRF1_1AB_P") (class "Default")
      (node (ref "IC5") (pin "B8") (pinfunction "pa1op_1_B8") (pintype "passive"))
      (node (ref "MN80") (pin "1") (pinfunction "1_1") (pintype "passive"))
      (node (ref "MN82") (pin "2") (pinfunction "2_2") (pintype "passive"))
      (node (ref "MN83") (pin "1") (pinfunction "1_1") (pintype "passive"))
    )
    (net (code "31") (name "/LMS3_TXRF1_1BB_N") (class "Default")
      (node (ref "MN85") (pin "1") (pinfunction "1_1") (pintype "passive"))
      (node (ref "MN88") (pin "1") (pinfunction "1_1") (pintype "passive"))
      (node (ref "T14") (pin "6") (pinfunction "6_6") (pintype "passive"))
    )
    (net (code "32") (name "/LMS3_TXRF1_1BB_P") (class "Default")
      (node (ref "MN82") (pin "1") (pinfunction "1_1") (pintype "passive"))
      (node (ref "MN85") (pin "2") (pinfunction "2_2") (pintype "passive"))
      (node (ref "T14") (pin "4") (pinfunction "4_4") (pintype "passive"))
    )
    (net (code "33") (name "/LMS3_TXRF2_1AB_N") (class "Default")
      (node (ref "IC5") (pin "C11") (pinfunction "pa1on_2_C11") (pintype "passive"))
      (node (ref "MN77") (pin "1") (pinfunction "1_1") (pintype "passive"))
      (node (ref "MN86") (pin "1") (pinfunction "1_1") (pintype "passive"))
      (node (ref "MN87") (pin "2") (pinfunction "2_2") (pintype "passive"))
    )
    (net (code "34") (name "/LMS3_TXRF2_1AB_P") (class "Default")
      (node (ref "IC5") (pin "B12") (pinfunction "pa1op_2_B12") (pintype "passive"))
      (node (ref "MN78") (pin "1") (pinfunction "1_1") (pintype "passive"))
      (node (ref "MN81") (pin "2") (pinfunction "2_2") (pintype "passive"))
      (node (ref "MN86") (pin "2") (pinfunction "2_2") (pintype "passive"))
    )
    (net (code "35") (name "/LMS3_TXRF2_1BB_N") (class "Default")
      (node (ref "MN84") (pin "1") (pinfunction "1_1") (pintype "passive"))
      (node (ref "MN87") (pin "1") (pinfunction "1_1") (pintype "passive"))
      (node (ref "T13") (pin "6") (pinfunction "6_6") (pintype "passive"))
    )
    (net (code "36") (name "/LMS3_TXRF2_1BB_P") (class "Default")
      (node (ref "MN81") (pin "1") (pinfunction "1_1") (pintype "passive"))
      (node (ref "MN84") (pin "2") (pinfunction "2_2") (pintype "passive"))
      (node (ref "T13") (pin "4") (pinfunction "4_4") (pintype "passive"))
    )
    (net (code "37") (name "/LMS3_TXRF2_2AB_N") (class "Default")
      (node (ref "IC5") (pin "B14") (pinfunction "pa2on_2_B14") (pintype "passive"))
      (node (ref "MN91") (pin "1") (pinfunction "1_1") (pintype "passive"))
      (node (ref "MN94") (pin "1") (pinfunction "1_1") (pintype "passive"))
      (node (ref "MN96") (pin "1") (pinfunction "1_1") (pintype "passive"))
    )
    (net (code "38") (name "/LMS3_TXRF2_2AB_P") (class "Default")
      (node (ref "IC5") (pin "A13") (pinfunction "pa2op_2_A13") (pintype "passive"))
      (node (ref "MN92") (pin "1") (pinfunction "1_1") (pintype "passive"))
      (node (ref "MN93") (pin "2") (pinfunction "2_2") (pintype "passive"))
      (node (ref "MN94") (pin "2") (pinfunction "2_2") (pintype "passive"))
    )
    (net (code "39") (name "/LMS3_TXRF2_2BB_N") (class "Default")
      (node (ref "MN95") (pin "1") (pinfunction "1_1") (pintype "passive"))
      (node (ref "MN96") (pin "2") (pinfunction "2_2") (pintype "passive"))
      (node (ref "T15") (pin "4") (pinfunction "4_4") (pintype "passive"))
    )
    (net (code "40") (name "/LMS3_TXRF2_2BB_P") (class "Default")
      (node (ref "MN93") (pin "1") (pinfunction "1_1") (pintype "passive"))
      (node (ref "MN95") (pin "2") (pinfunction "2_2") (pintype "passive"))
      (node (ref "T15") (pin "6") (pinfunction "6_6") (pintype "passive"))
    )
    (net (code "41") (name "/RFSW1_LMS3_RX1_V1") (class "Default")
      (node (ref "C78") (pin "1") (pinfunction "1_1") (pintype "passive"))
      (node (ref "IC11") (pin "10") (pinfunction "V1_10") (pintype "input"))
    )
    (net (code "42") (name "/RFSW1_LMS3_RX2_V1") (class "Default")
      (node (ref "C79") (pin "1") (pinfunction "1_1") (pintype "passive"))
      (node (ref "IC12") (pin "10") (pinfunction "V1_10") (pintype "input"))
    )
    (net (code "43") (name "GND") (class "Default")
      (node (ref "C55") (pin "1") (pinfunction "1_1") (pintype "passive"))
      (node (ref "C56") (pin "1") (pinfunction "1_1") (pintype "passive"))
      (node (ref "C57") (pin "1") (pinfunction "1_1") (pintype "passive"))
      (node (ref "C58") (pin "1") (pinfunction "1_1") (pintype "passive"))
      (node (ref "C59") (pin "1") (pinfunction "1_1") (pintype "passive"))
      (node (ref "C60") (pin "1") (pinfunction "1_1") (pintype "passive"))
      (node (ref "C61") (pin "1") (pinfunction "1_1") (pintype "passive"))
      (node (ref "C62") (pin "1") (pinfunction "1_1") (pintype "passive"))
      (node (ref "C65") (pin "1") (pinfunction "1_1") (pintype "passive"))
      (node (ref "C66") (pin "1") (pinfunction "1_1") (pintype "passive"))
      (node (ref "C67") (pin "1") (pinfunction "1_1") (pintype "passive"))
      (node (ref "C68") (pin "1") (pinfunction "1_1") (pintype "passive"))
      (node (ref "C78") (pin "2") (pinfunction "2_2") (pintype "passive"))
      (node (ref "C79") (pin "2") (pinfunction "2_2") (pintype "passive"))
      (node (ref "C80") (pin "1") (pinfunction "1_1") (pintype "passive"))
      (node (ref "C81") (pin "1") (pinfunction "1_1") (pintype "passive"))
      (node (ref "ESD3") (pin "2") (pinfunction "2_2") (pintype "passive"))
      (node (ref "ESD4") (pin "2") (pinfunction "2_2") (pintype "passive"))
      (node (ref "ESD5") (pin "2") (pinfunction "2_2") (pintype "passive"))
      (node (ref "ESD6") (pin "2") (pinfunction "2_2") (pintype "passive"))
      (node (ref "ESD7") (pin "2") (pinfunction "2_2") (pintype "passive"))
      (node (ref "IC11") (pin "1") (pinfunction "GND_1") (pintype "passive"))
      (node (ref "IC11") (pin "11") (pinfunction "LS_11") (pintype "input"))
      (node (ref "IC11") (pin "3") (pinfunction "GND_3") (pintype "passive"))
      (node (ref "IC11") (pin "4") (pinfunction "GND/NC_4") (pintype "passive"))
      (node (ref "IC11") (pin "6") (pinfunction "GND_6") (pintype "passive"))
      (node (ref "IC11") (pin "7") (pinfunction "GND_7") (pintype "passive"))
      (node (ref "IC11") (pin "9") (pinfunction "DGND_9") (pintype "passive"))
      (node (ref "IC11") (pin "PAD") (pinfunction "PAD_PAD") (pintype "passive"))
      (node (ref "IC12") (pin "1") (pinfunction "GND_1") (pintype "passive"))
      (node (ref "IC12") (pin "11") (pinfunction "LS_11") (pintype "input"))
      (node (ref "IC12") (pin "3") (pinfunction "GND_3") (pintype "passive"))
      (node (ref "IC12") (pin "4") (pinfunction "GND/NC_4") (pintype "passive"))
      (node (ref "IC12") (pin "6") (pinfunction "GND_6") (pintype "passive"))
      (node (ref "IC12") (pin "7") (pinfunction "GND_7") (pintype "passive"))
      (node (ref "IC12") (pin "9") (pinfunction "DGND_9") (pintype "passive"))
      (node (ref "IC12") (pin "PAD") (pinfunction "PAD_PAD") (pintype "passive"))
      (node (ref "IC5") (pin "AJ7") (pinfunction "rfsn_l_RFE_2_AJ7") (pintype "passive"))
      (node (ref "IC5") (pin "AJ9") (pinfunction "rfsp_l_RFE_2_AJ9") (pintype "passive"))
      (node (ref "IC5") (pin "AK12") (pinfunction "rfsn_l_RFE_1_AK12") (pintype "passive"))
      (node (ref "IC5") (pin "AL13") (pinfunction "rfsp_l_RFE_1_AL13") (pintype "passive"))
      (node (ref "IC5") (pin "AM12") (pinfunction "rfgn_l_RFE_1_AM12") (pintype "passive"))
      (node (ref "IC5") (pin "AN11") (pinfunction "rfgp_l_RFE_1_AN11") (pintype "passive"))
      (node (ref "IC5") (pin "AN5") (pinfunction "rfgp_l_RFE_2_AN5") (pintype "passive"))
      (node (ref "IC5") (pin "AP6") (pinfunction "rfgn_l_RFE_2_AP6") (pintype "passive"))
      (node (ref "J3") (pin "2") (pinfunction "Y_2") (pintype "passive"))
      (node (ref "J4") (pin "2") (pinfunction "Y_2") (pintype "passive"))
      (node (ref "J5") (pin "2") (pinfunction "Y_2") (pintype "passive"))
      (node (ref "J6") (pin "2") (pinfunction "Y_2") (pintype "passive"))
      (node (ref "J7") (pin "2") (pinfunction "Y_2") (pintype "passive"))
      (node (ref "T13") (pin "2") (pinfunction "2_2") (pintype "passive"))
      (node (ref "T14") (pin "2") (pinfunction "2_2") (pintype "passive"))
      (node (ref "T15") (pin "3") (pinfunction "3_3") (pintype "passive"))
      (node (ref "T16") (pin "2") (pinfunction "2_2") (pintype "passive"))
      (node (ref "T17") (pin "2") (pinfunction "2_2") (pintype "passive"))
      (node (ref "T18") (pin "1") (pinfunction "1_1") (pintype "passive"))
      (node (ref "T19") (pin "3") (pinfunction "3_3") (pintype "passive"))
    )
    (net (code "44") (name "Net-(C63-Pad2)") (class "Default")
      (node (ref "C63") (pin "2") (pinfunction "2_2") (pintype "passive"))
      (node (ref "T13") (pin "3") (pinfunction "3_3") (pintype "passive"))
    )
    (net (code "45") (name "Net-(C64-Pad2)") (class "Default")
      (node (ref "C64") (pin "2") (pinfunction "2_2") (pintype "passive"))
      (node (ref "T14") (pin "3") (pinfunction "3_3") (pintype "passive"))
    )
    (net (code "46") (name "Net-(C69-Pad2)") (class "Default")
      (node (ref "C69") (pin "2") (pinfunction "2_2") (pintype "passive"))
      (node (ref "T15") (pin "1") (pinfunction "1_1") (pintype "passive"))
    )
    (net (code "47") (name "Net-(C70-Pad2)") (class "Default")
      (node (ref "C70") (pin "2") (pinfunction "2_2") (pintype "passive"))
      (node (ref "T16") (pin "3") (pinfunction "3_3") (pintype "passive"))
    )
    (net (code "48") (name "Net-(C71-Pad2)") (class "Default")
      (node (ref "C71") (pin "2") (pinfunction "2_2") (pintype "passive"))
      (node (ref "T17") (pin "3") (pinfunction "3_3") (pintype "passive"))
    )
    (net (code "49") (name "Net-(C72-Pad2)") (class "Default")
      (node (ref "C72") (pin "2") (pinfunction "2_2") (pintype "passive"))
      (node (ref "T18") (pin "3") (pinfunction "3_3") (pintype "passive"))
    )
    (net (code "50") (name "Net-(C73-Pad2)") (class "Default")
      (node (ref "C73") (pin "2") (pinfunction "2_2") (pintype "passive"))
      (node (ref "T19") (pin "1") (pinfunction "1_1") (pintype "passive"))
    )
    (net (code "51") (name "Net-(IC11-RF1)") (class "Default")
      (node (ref "C76") (pin "1") (pinfunction "1_1") (pintype "passive"))
      (node (ref "IC11") (pin "8") (pinfunction "RF1_8") (pintype "bidirectional"))
    )
    (net (code "52") (name "Net-(IC11-RF2)") (class "Default")
      (node (ref "C74") (pin "1") (pinfunction "1_1") (pintype "passive"))
      (node (ref "IC11") (pin "2") (pinfunction "RF2_2") (pintype "bidirectional"))
    )
    (net (code "53") (name "Net-(IC12-RF1)") (class "Default")
      (node (ref "C77") (pin "1") (pinfunction "1_1") (pintype "passive"))
      (node (ref "IC12") (pin "8") (pinfunction "RF1_8") (pintype "bidirectional"))
    )
    (net (code "54") (name "Net-(IC12-RF2)") (class "Default")
      (node (ref "C75") (pin "1") (pinfunction "1_1") (pintype "passive"))
      (node (ref "IC12") (pin "2") (pinfunction "RF2_2") (pintype "bidirectional"))
    )
    (net (code "55") (name "Net-(MN73-Pad1)") (class "Default")
      (node (ref "MN73") (pin "1") (pinfunction "1_1") (pintype "passive"))
      (node (ref "MN77") (pin "2") (pinfunction "2_2") (pintype "passive"))
    )
    (net (code "56") (name "Net-(MN74-Pad1)") (class "Default")
      (node (ref "MN74") (pin "1") (pinfunction "1_1") (pintype "passive"))
      (node (ref "MN78") (pin "2") (pinfunction "2_2") (pintype "passive"))
    )
    (net (code "57") (name "Net-(MN75-Pad1)") (class "Default")
      (node (ref "MN75") (pin "1") (pinfunction "1_1") (pintype "passive"))
      (node (ref "MN79") (pin "2") (pinfunction "2_2") (pintype "passive"))
    )
    (net (code "58") (name "Net-(MN76-Pad1)") (class "Default")
      (node (ref "MN76") (pin "1") (pinfunction "1_1") (pintype "passive"))
      (node (ref "MN80") (pin "2") (pinfunction "2_2") (pintype "passive"))
    )
    (net (code "59") (name "Net-(MN89-Pad1)") (class "Default")
      (node (ref "MN89") (pin "1") (pinfunction "1_1") (pintype "passive"))
      (node (ref "MN91") (pin "2") (pinfunction "2_2") (pintype "passive"))
    )
    (net (code "60") (name "Net-(MN90-Pad1)") (class "Default")
      (node (ref "MN90") (pin "1") (pinfunction "1_1") (pintype "passive"))
      (node (ref "MN92") (pin "2") (pinfunction "2_2") (pintype "passive"))
    )
    (net (code "61") (name "VCC1P8_LMS3") (class "Default")
      (node (ref "C55") (pin "2") (pinfunction "2_2") (pintype "passive"))
      (node (ref "C56") (pin "2") (pinfunction "2_2") (pintype "passive"))
      (node (ref "C57") (pin "2") (pinfunction "2_2") (pintype "passive"))
      (node (ref "C58") (pin "2") (pinfunction "2_2") (pintype "passive"))
      (node (ref "C59") (pin "2") (pinfunction "2_2") (pintype "passive"))
      (node (ref "C60") (pin "2") (pinfunction "2_2") (pintype "passive"))
      (node (ref "C61") (pin "2") (pinfunction "2_2") (pintype "passive"))
      (node (ref "C62") (pin "2") (pinfunction "2_2") (pintype "passive"))
      (node (ref "C65") (pin "2") (pinfunction "2_2") (pintype "passive"))
      (node (ref "C66") (pin "2") (pinfunction "2_2") (pintype "passive"))
      (node (ref "C67") (pin "2") (pinfunction "2_2") (pintype "passive"))
      (node (ref "C68") (pin "2") (pinfunction "2_2") (pintype "passive"))
      (node (ref "MN73") (pin "2") (pinfunction "2_2") (pintype "passive"))
      (node (ref "MN74") (pin "2") (pinfunction "2_2") (pintype "passive"))
      (node (ref "MN75") (pin "2") (pinfunction "2_2") (pintype "passive"))
      (node (ref "MN76") (pin "2") (pinfunction "2_2") (pintype "passive"))
      (node (ref "MN89") (pin "2") (pinfunction "2_2") (pintype "passive"))
      (node (ref "MN90") (pin "2") (pinfunction "2_2") (pintype "passive"))
    )
    (net (code "62") (name "VCC3P3_RF") (class "Default")
      (node (ref "C80") (pin "2") (pinfunction "2_2") (pintype "passive"))
      (node (ref "C81") (pin "2") (pinfunction "2_2") (pintype "passive"))
      (node (ref "IC11") (pin "12") (pinfunction "VDD_12") (pintype "power_in"))
      (node (ref "IC12") (pin "12") (pinfunction "VDD_12") (pintype "power_in"))
    )
    (net (code "63") (name "unconnected-(IC5C-pa2on_1-PadB10)") (class "Default")
      (node (ref "IC5") (pin "B10") (pinfunction "pa2on_1_B10") (pintype "passive+no_connect"))
    )
    (net (code "64") (name "unconnected-(IC5C-pa2op_1-PadA9)") (class "Default")
      (node (ref "IC5") (pin "A9") (pinfunction "pa2op_1_A9") (pintype "passive+no_connect"))
    )
    (net (code "65") (name "unconnected-(T15-Pad2)") (class "Default")
      (node (ref "T15") (pin "2") (pinfunction "2_2") (pintype "passive+no_connect"))
    )
    (net (code "66") (name "unconnected-(T18-Pad2)") (class "Default")
      (node (ref "T18") (pin "2") (pinfunction "2_2") (pintype "passive+no_connect"))
    )
    (net (code "67") (name "unconnected-(T19-Pad2)") (class "Default")
      (node (ref "T19") (pin "2") (pinfunction "2_2") (pintype "passive+no_connect"))
    )
  )
)
